# ASL1002.net
KiCad netlist of a schematic drawn in EAGLE
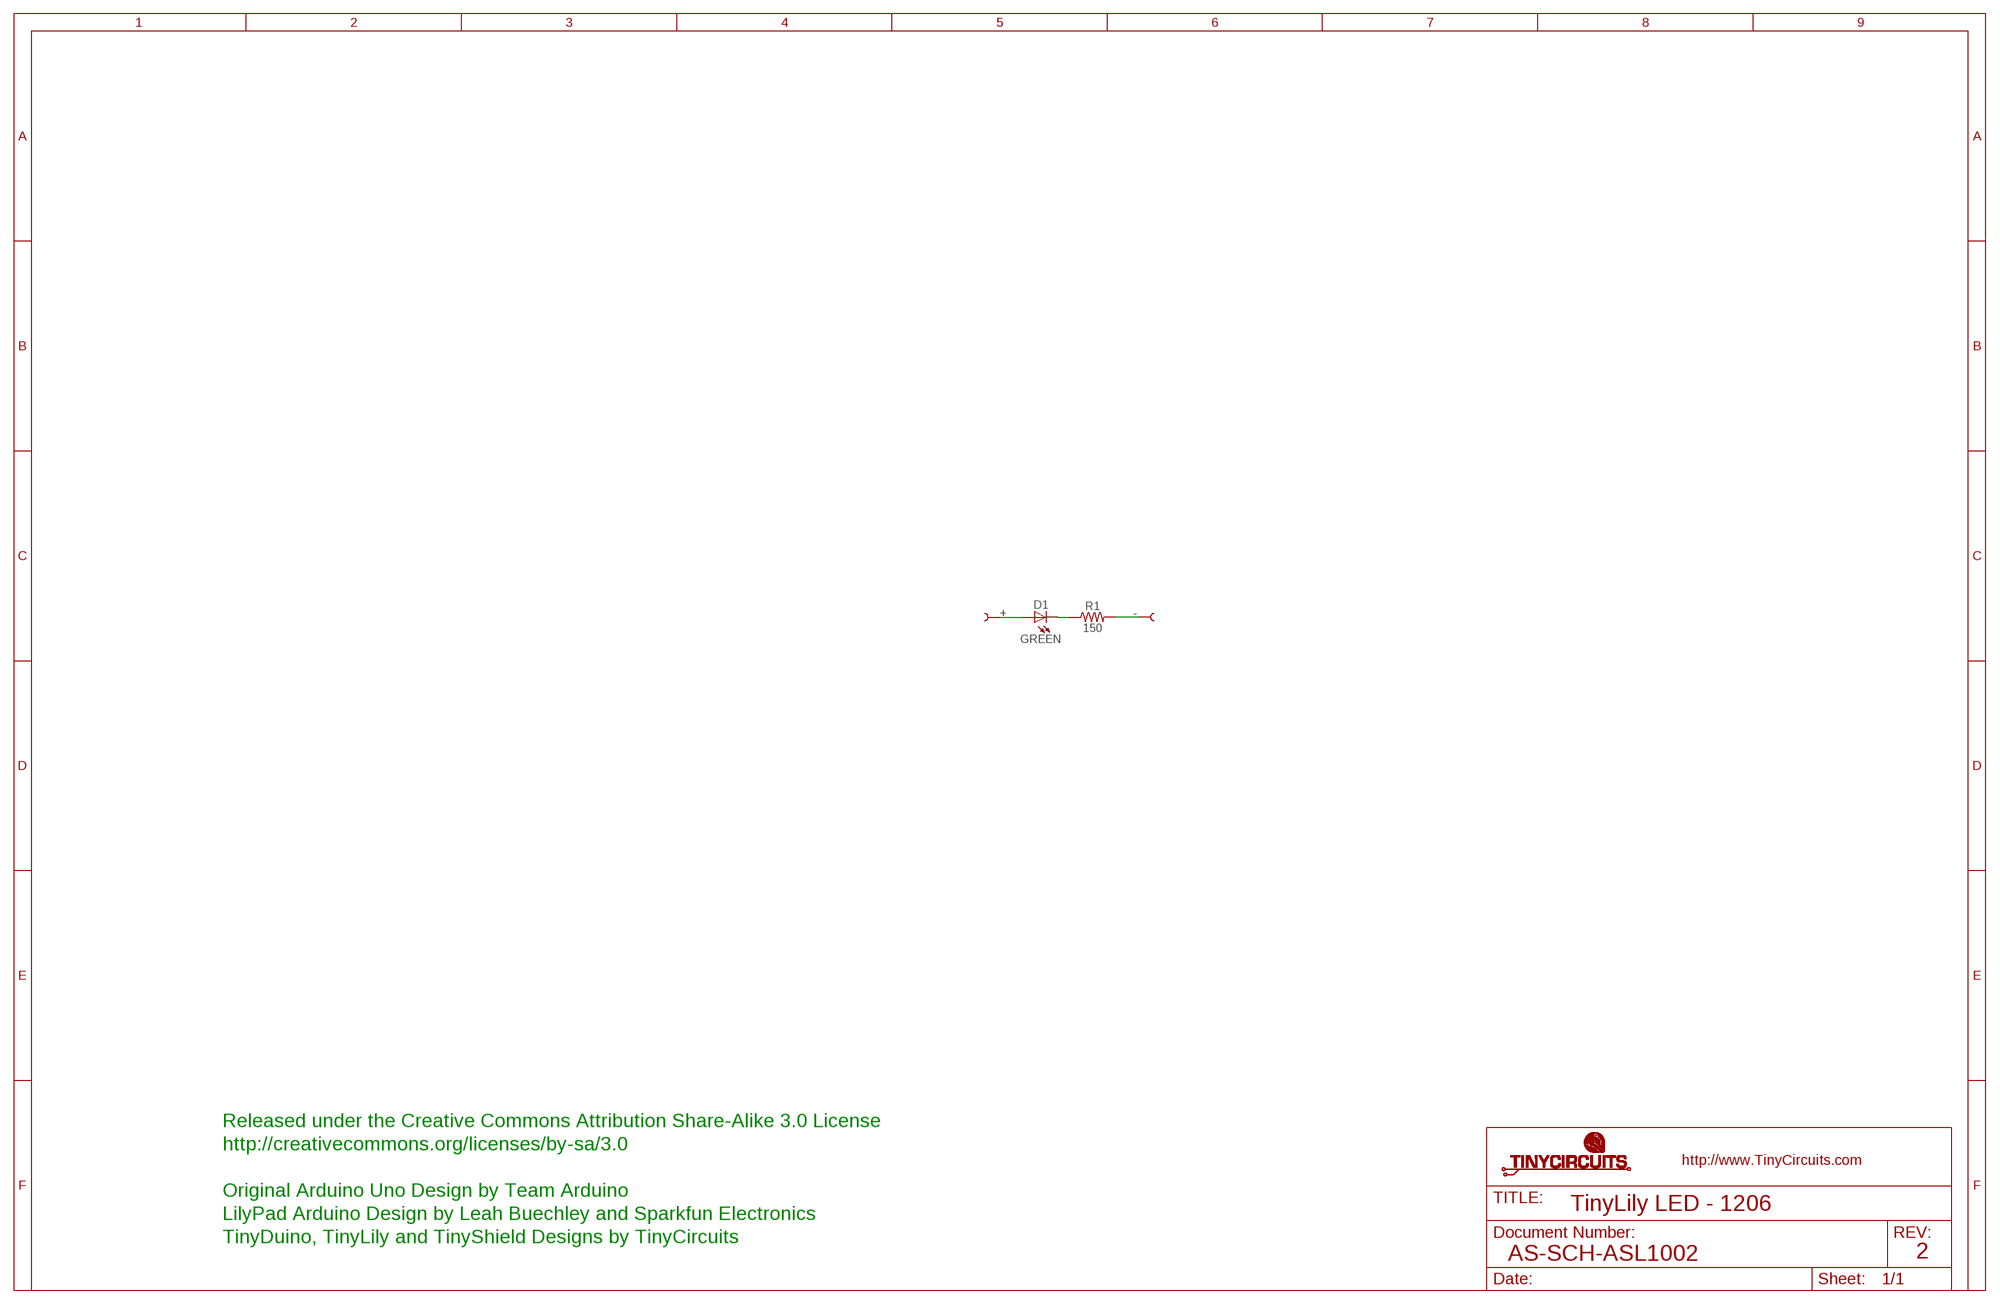
[diagram p0: schematic, sheet 1]

(export (version "E")
  (design (tool "Eeschema 10.0.6"))
  (components
    (comp (ref "D1")
      (value "GREEN")
      (footprint "eagle-import:1206_LED")
      (fields (field (name "PARTNO") "AS-ITM-00039") (field (name "PARTNO_1") "AS-ITM-00039"))
      (libsource (lib "eagle-import") (part "AS-ITM-00039"))
    )
    (comp (ref "R1")
      (value "150")
      (footprint "eagle-import:R0805")
      (fields (field (name "PARTNO") "AS-ITM-00040"))
      (libsource (lib "eagle-import") (part "AS-ITM-00040"))
    )
    (comp (ref "U$1")
      (value "SEWTABTH_1206")
      (footprint "eagle-import:SEWTAP_TH_1206")
      (libsource (lib "eagle-import") (part "SEWTABTH_1206"))
    )
    (comp (ref "U$7")
      (value "SEWTABTH_1206")
      (footprint "eagle-import:SEWTAP_TH_1206")
      (libsource (lib "eagle-import") (part "SEWTABTH_1206"))
    )
  )
  (nets
    (net (code "1") (name "/+") (class "Default")
      (node (ref "D1") (pin "1") (pinfunction "A_1") (pintype "passive"))
      (node (ref "U$7") (pin "1") (pinfunction "1_1") (pintype "bidirectional"))
    )
    (net (code "2") (name "/-") (class "Default")
      (node (ref "R1") (pin "2") (pinfunction "2_2") (pintype "passive"))
      (node (ref "U$1") (pin "1") (pinfunction "1_1") (pintype "bidirectional"))
    )
    (net (code "3") (name "Net-(D1-C)") (class "Default")
      (node (ref "D1") (pin "2") (pinfunction "C_2") (pintype "passive"))
      (node (ref "R1") (pin "1") (pinfunction "1_1") (pintype "passive"))
    )
  )
)
